# ADC16b_Pressure.net
KiCad netlist of a schematic drawn in Altium Designer
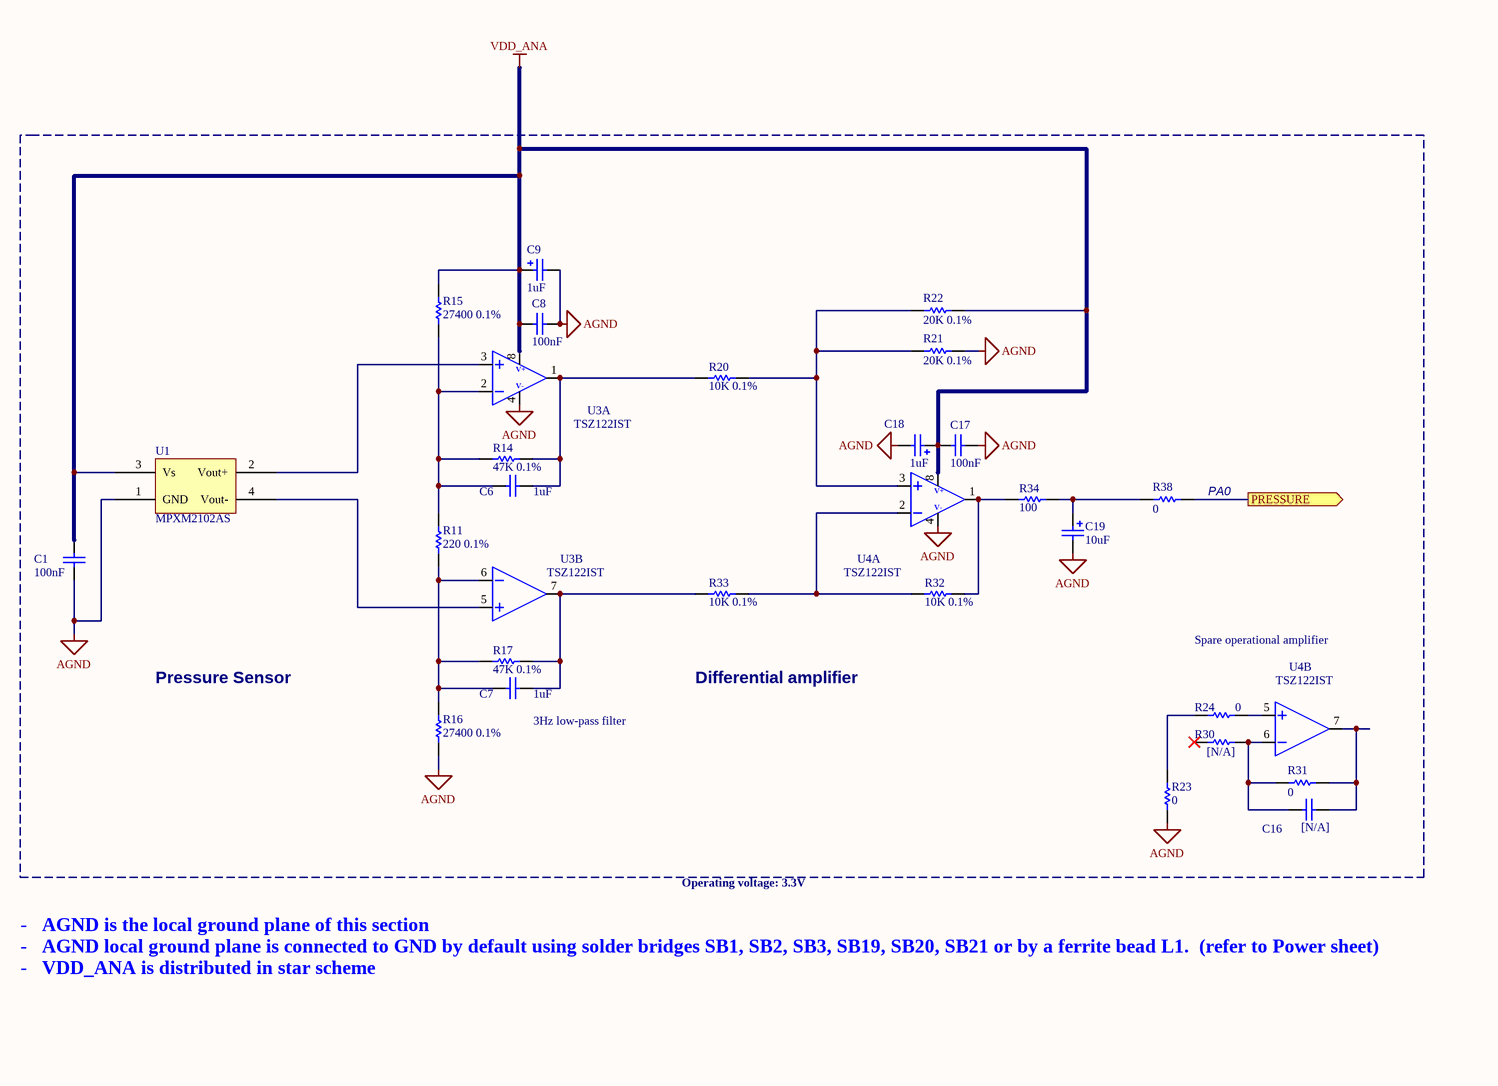
[diagram p0: ADC16b_Pressure.SchDoc]

(export (version "E")
  (design (tool "Eeschema 10.0.6"))
  (components
    (comp (ref "C1")
      (value "100nF")
      (footprint "0402C")
      (description "Capacitor")
      (fields (field (name "PUBLISHER") "Altium Limited"))
      (libsource (lib "Miscellaneous Devices") (part "CAP"))
    )
    (comp (ref "C6")
      (value "1uF")
      (footprint "0603C")
      (description "Capacitor")
      (fields (field (name "PUBLISHER") "Altium Limited"))
      (libsource (lib "Miscellaneous Devices") (part "CAP"))
    )
    (comp (ref "C7")
      (value "1uF")
      (footprint "0603C")
      (description "Capacitor")
      (fields (field (name "PUBLISHER") "Altium Limited"))
      (libsource (lib "Miscellaneous Devices") (part "CAP"))
    )
    (comp (ref "C8")
      (value "100nF")
      (footprint "0402C")
      (description "Capacitor")
      (fields (field (name "PUBLISHER") "Altium Limited"))
      (libsource (lib "Miscellaneous Devices") (part "CAP"))
    )
    (comp (ref "C9")
      (value "1uF")
      (footprint "TAN-A")
      (description "Polarized Capacitor")
      (fields (field (name "PUBLISHER") "Altium Limited"))
      (libsource (lib "Miscellaneous Devices") (part "Cap Pol1"))
    )
    (comp (ref "C16")
      (value "[N/A]")
      (footprint "0603C")
      (description "Capacitor")
      (fields (field (name "PUBLISHER") "Altium Limited"))
      (libsource (lib "Miscellaneous Devices") (part "cap"))
    )
    (comp (ref "C17")
      (value "100nF")
      (footprint "0402C")
      (description "Capacitor")
      (fields (field (name "PUBLISHER") "Altium Limited"))
      (libsource (lib "Miscellaneous Devices") (part "CAP"))
    )
    (comp (ref "C18")
      (value "1uF")
      (footprint "TAN-A")
      (description "Polarized Capacitor")
      (fields (field (name "PUBLISHER") "Altium Limited"))
      (libsource (lib "Miscellaneous Devices") (part "Cap Pol1"))
    )
    (comp (ref "C19")
      (value "10uF")
      (footprint "TAN-A")
      (description "Polarized Capacitor (Radial)")
      (fields (field (name "PUBLISHER") "Altium Limited"))
      (libsource (lib "Miscellaneous Devices") (part "Cap Pol1"))
    )
    (comp (ref "R11")
      (value "220 0.1%")
      (footprint "0603R")
      (description "Resistor")
      (fields (field (name "PUBLISHER") "Altium Limited"))
      (libsource (lib "Miscellaneous Devices") (part "Res1"))
    )
    (comp (ref "R14")
      (value "47K 0.1%")
      (footprint "0603R")
      (description "Resistor")
      (fields (field (name "PUBLISHER") "Altium Limited"))
      (libsource (lib "Miscellaneous Devices") (part "Res1"))
    )
    (comp (ref "R15")
      (value "27400 0.1%")
      (footprint "0603R")
      (description "Resistor")
      (fields (field (name "PUBLISHER") "Altium Limited"))
      (libsource (lib "Miscellaneous Devices") (part "Res1"))
    )
    (comp (ref "R16")
      (value "27400 0.1%")
      (footprint "0603R")
      (description "Resistor")
      (fields (field (name "PUBLISHER") "Altium Limited"))
      (libsource (lib "Miscellaneous Devices") (part "Res1"))
    )
    (comp (ref "R17")
      (value "47K 0.1%")
      (footprint "0603R")
      (description "Resistor")
      (fields (field (name "PUBLISHER") "Altium Limited"))
      (libsource (lib "Miscellaneous Devices") (part "Res1"))
    )
    (comp (ref "R20")
      (value "10K 0.1%")
      (footprint "0603R")
      (description "Resistor")
      (fields (field (name "PUBLISHER") "Altium Limited"))
      (libsource (lib "Miscellaneous Devices") (part "Res1"))
    )
    (comp (ref "R21")
      (value "20K 0.1%")
      (footprint "0603R")
      (description "Resistor")
      (fields (field (name "PUBLISHER") "Altium Limited"))
      (libsource (lib "Miscellaneous Devices") (part "Res1"))
    )
    (comp (ref "R22")
      (value "20K 0.1%")
      (footprint "0603R")
      (description "Resistor")
      (fields (field (name "PUBLISHER") "Altium Limited"))
      (libsource (lib "Miscellaneous Devices") (part "Res1"))
    )
    (comp (ref "R23")
      (value "0")
      (footprint "0603R")
      (description "Resistor")
      (fields (field (name "PUBLISHER") "Altium Limited"))
      (libsource (lib "Miscellaneous Devices") (part "Res1"))
    )
    (comp (ref "R24")
      (value "0")
      (footprint "0603R")
      (description "Resistor")
      (fields (field (name "PUBLISHER") "Altium Limited"))
      (libsource (lib "Miscellaneous Devices") (part "Res1"))
    )
    (comp (ref "R30")
      (value "[N/A]")
      (footprint "0603R")
      (description "Resistor")
      (fields (field (name "PUBLISHER") "Altium Limited"))
      (libsource (lib "Miscellaneous Devices") (part "Res1"))
    )
    (comp (ref "R31")
      (value "0")
      (footprint "0603R")
      (description "Resistor")
      (fields (field (name "PUBLISHER") "Altium Limited"))
      (libsource (lib "Miscellaneous Devices") (part "Res1"))
    )
    (comp (ref "R32")
      (value "10K 0.1%")
      (footprint "0603R")
      (description "Resistor")
      (fields (field (name "PUBLISHER") "Altium Limited"))
      (libsource (lib "Miscellaneous Devices") (part "Res1"))
    )
    (comp (ref "R33")
      (value "10K 0.1%")
      (footprint "0603R")
      (description "Resistor")
      (fields (field (name "PUBLISHER") "Altium Limited"))
      (libsource (lib "Miscellaneous Devices") (part "Res1"))
    )
    (comp (ref "R34")
      (value "100")
      (footprint "0402R")
      (description "Resistor")
      (fields (field (name "PUBLISHER") "Altium Limited"))
      (libsource (lib "Miscellaneous Devices") (part "Res1"))
    )
    (comp (ref "R38")
      (value "0")
      (footprint "0603R")
      (description "Resistor")
      (fields (field (name "PUBLISHER") "Altium Limited"))
      (libsource (lib "Miscellaneous Devices") (part "Res1"))
    )
    (comp (ref "U1")
      (value "MPXM2102AS")
      (footprint "SENSOR_MPXM2102AS")
      (libsource (lib "MB988") (part "MPX2102"))
    )
    (comp (ref "U3")
      (value "TSZ122IST")
      (footprint "MSOP8_0R65_3X4R9")
      (libsource (lib "") (part "AOP-8PINS_1"))
    )
    (comp (ref "U4")
      (value "TSZ122IST")
      (footprint "MSOP8_0R65_3X4R9")
      (libsource (lib "") (part "AOP-8PINS_1"))
    )
  )
  (nets
    (net (code "1") (name "/PRESSURE") (class "Default")
      (node (ref "R38") (pin "2") (pinfunction "2_2") (pintype "passive"))
    )
    (net (code "2") (name "AGND") (class "Default")
      (node (ref "C1") (pin "1") (pinfunction "1_1") (pintype "passive"))
      (node (ref "C17") (pin "1") (pinfunction "1_1") (pintype "passive"))
      (node (ref "C18") (pin "2") (pinfunction "2_2") (pintype "passive"))
      (node (ref "C19") (pin "2") (pinfunction "2_2") (pintype "passive"))
      (node (ref "C8") (pin "1") (pinfunction "1_1") (pintype "passive"))
      (node (ref "C9") (pin "2") (pinfunction "2_2") (pintype "passive"))
      (node (ref "R16") (pin "2") (pinfunction "2_2") (pintype "passive"))
      (node (ref "R21") (pin "2") (pinfunction "2_2") (pintype "passive"))
      (node (ref "R23") (pin "2") (pinfunction "2_2") (pintype "passive"))
      (node (ref "U1") (pin "1") (pinfunction "GND_1") (pintype "passive"))
      (node (ref "U3") (pin "4") (pintype "passive"))
      (node (ref "U4") (pin "4") (pintype "passive"))
    )
    (net (code "3") (name "Net-(C6-Pad1)") (class "Default")
      (node (ref "C6") (pin "1") (pinfunction "1_1") (pintype "passive"))
      (node (ref "R11") (pin "1") (pinfunction "1_1") (pintype "passive"))
      (node (ref "R14") (pin "2") (pinfunction "2_2") (pintype "passive"))
      (node (ref "R15") (pin "2") (pinfunction "2_2") (pintype "passive"))
      (node (ref "U3") (pin "2") (pintype "passive"))
    )
    (net (code "4") (name "Net-(C6-Pad2)") (class "Default")
      (node (ref "C6") (pin "2") (pinfunction "2_2") (pintype "passive"))
      (node (ref "R14") (pin "1") (pinfunction "1_1") (pintype "passive"))
      (node (ref "R20") (pin "2") (pinfunction "2_2") (pintype "passive"))
      (node (ref "U3") (pin "1") (pintype "passive"))
    )
    (net (code "5") (name "Net-(C7-Pad1)") (class "Default")
      (node (ref "C7") (pin "1") (pinfunction "1_1") (pintype "passive"))
      (node (ref "R11") (pin "2") (pinfunction "2_2") (pintype "passive"))
      (node (ref "R16") (pin "1") (pinfunction "1_1") (pintype "passive"))
      (node (ref "R17") (pin "2") (pinfunction "2_2") (pintype "passive"))
      (node (ref "U3") (pin "6") (pintype "passive"))
    )
    (net (code "6") (name "Net-(C7-Pad2)") (class "Default")
      (node (ref "C7") (pin "2") (pinfunction "2_2") (pintype "passive"))
      (node (ref "R17") (pin "1") (pinfunction "1_1") (pintype "passive"))
      (node (ref "R33") (pin "2") (pinfunction "2_2") (pintype "passive"))
      (node (ref "U3") (pin "7") (pintype "passive"))
    )
    (net (code "7") (name "Net-(C16-Pad1)") (class "Default")
      (node (ref "C16") (pin "1") (pinfunction "1_1") (pintype "passive"))
      (node (ref "R31") (pin "1") (pinfunction "1_1") (pintype "passive"))
      (node (ref "U4") (pin "7") (pintype "passive"))
    )
    (net (code "8") (name "Net-(C16-Pad2)") (class "Default")
      (node (ref "C16") (pin "2") (pinfunction "2_2") (pintype "passive"))
      (node (ref "R30") (pin "1") (pinfunction "1_1") (pintype "passive"))
      (node (ref "R31") (pin "2") (pinfunction "2_2") (pintype "passive"))
      (node (ref "U4") (pin "6") (pintype "passive"))
    )
    (net (code "9") (name "Net-(C19-Pad1)") (class "Default")
      (node (ref "C19") (pin "1") (pinfunction "1_1") (pintype "passive"))
      (node (ref "R34") (pin "1") (pinfunction "1_1") (pintype "passive"))
      (node (ref "R38") (pin "1") (pinfunction "1_1") (pintype "passive"))
    )
    (net (code "10") (name "Net-(R20-Pad1)") (class "Default")
      (node (ref "R20") (pin "1") (pinfunction "1_1") (pintype "passive"))
      (node (ref "R21") (pin "1") (pinfunction "1_1") (pintype "passive"))
      (node (ref "R22") (pin "1") (pinfunction "1_1") (pintype "passive"))
      (node (ref "U4") (pin "3") (pintype "passive"))
    )
    (net (code "11") (name "Net-(R23-Pad1)") (class "Default")
      (node (ref "R23") (pin "1") (pinfunction "1_1") (pintype "passive"))
      (node (ref "R24") (pin "2") (pinfunction "2_2") (pintype "passive"))
    )
    (net (code "12") (name "Net-(R24-Pad1)") (class "Default")
      (node (ref "R24") (pin "1") (pinfunction "1_1") (pintype "passive"))
      (node (ref "U4") (pin "5") (pintype "passive"))
    )
    (net (code "13") (name "Net-(R32-Pad1)") (class "Default")
      (node (ref "R32") (pin "1") (pinfunction "1_1") (pintype "passive"))
      (node (ref "R34") (pin "2") (pinfunction "2_2") (pintype "passive"))
      (node (ref "U4") (pin "1") (pintype "passive"))
    )
    (net (code "14") (name "Net-(R32-Pad2)") (class "Default")
      (node (ref "R32") (pin "2") (pinfunction "2_2") (pintype "passive"))
      (node (ref "R33") (pin "1") (pinfunction "1_1") (pintype "passive"))
      (node (ref "U4") (pin "2") (pintype "passive"))
    )
    (net (code "15") (name "Net-(U1-Vout+)") (class "Default")
      (node (ref "U1") (pin "2") (pinfunction "Vout+_2") (pintype "passive"))
      (node (ref "U3") (pin "3") (pintype "passive"))
    )
    (net (code "16") (name "Net-(U1-Vout-)") (class "Default")
      (node (ref "U1") (pin "4") (pinfunction "Vout-_4") (pintype "passive"))
      (node (ref "U3") (pin "5") (pintype "passive"))
    )
    (net (code "17") (name "VDD_ANA") (class "Default")
      (node (ref "C1") (pin "2") (pinfunction "2_2") (pintype "passive"))
      (node (ref "C17") (pin "2") (pinfunction "2_2") (pintype "passive"))
      (node (ref "C18") (pin "1") (pinfunction "1_1") (pintype "passive"))
      (node (ref "C8") (pin "2") (pinfunction "2_2") (pintype "passive"))
      (node (ref "C9") (pin "1") (pinfunction "1_1") (pintype "passive"))
      (node (ref "R15") (pin "1") (pinfunction "1_1") (pintype "passive"))
      (node (ref "R22") (pin "2") (pinfunction "2_2") (pintype "passive"))
      (node (ref "U1") (pin "3") (pinfunction "Vs_3") (pintype "passive"))
      (node (ref "U3") (pin "8") (pintype "passive"))
      (node (ref "U4") (pin "8") (pintype "passive"))
    )
    (net (code "18") (name "unconnected-(R30-Pad2)") (class "Default")
      (node (ref "R30") (pin "2") (pinfunction "2_2") (pintype "passive+no_connect"))
    )
  )
)
